# untitled.net
KiCad netlist of a schematic drawn in EAGLE
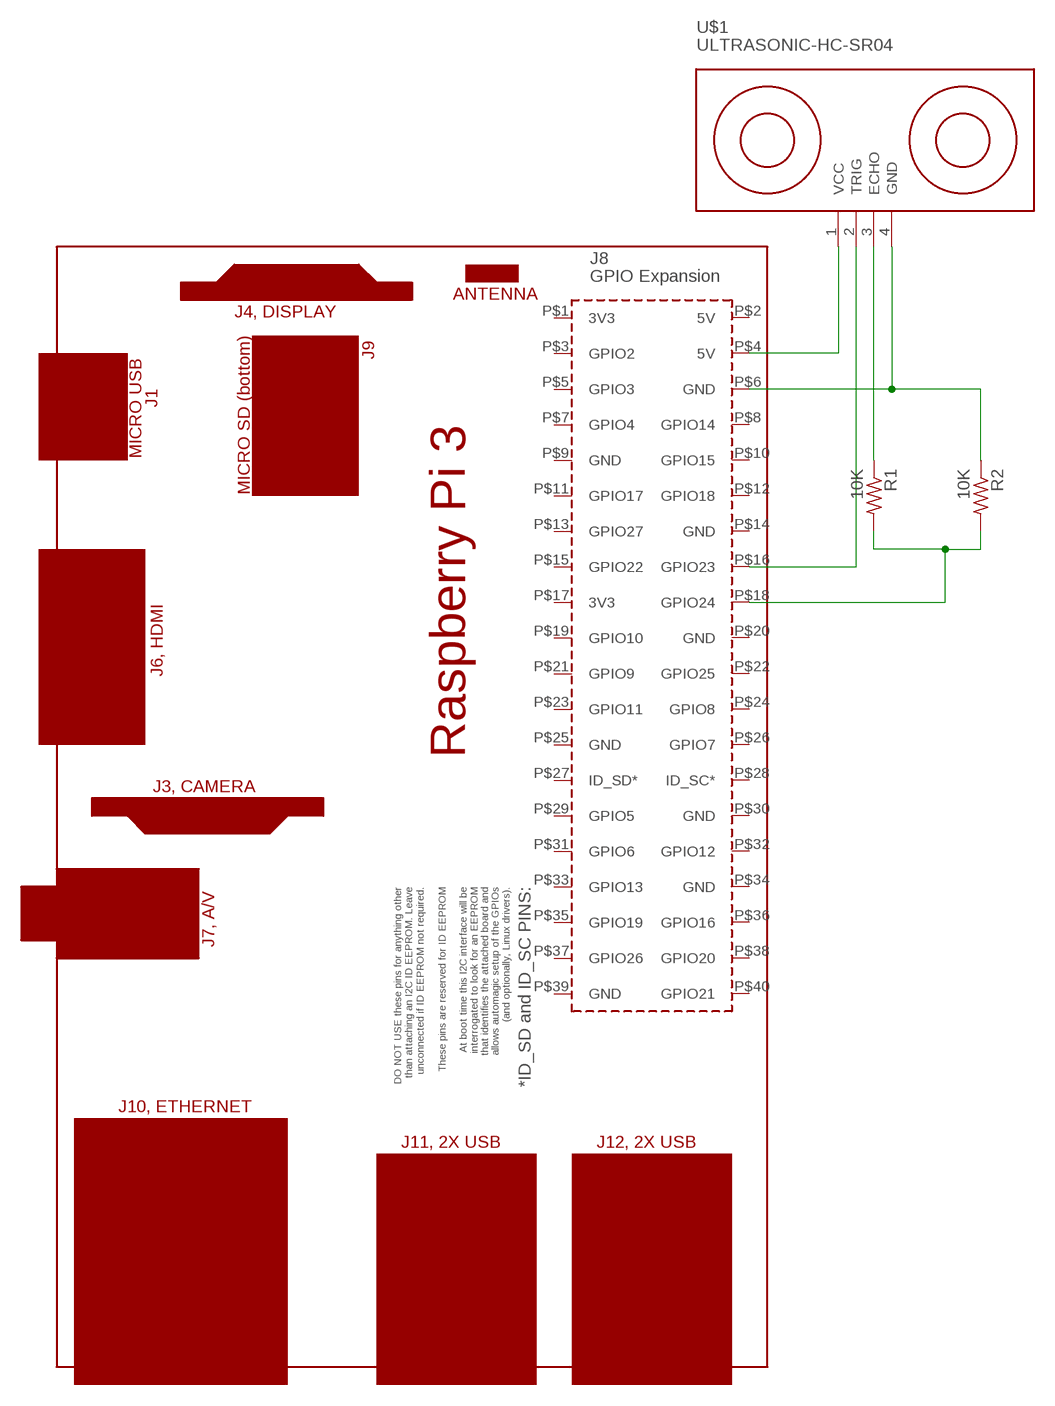
[diagram p0: schematic, sheet 1]

(export (version "E")
  (design (tool "Eeschema 10.0.6"))
  (components
    (comp (ref "PCB1")
      (value "RPI3RPI3")
      (footprint "eagle-import:RPI3")
      (libsource (lib "eagle-import") (part "RPI3RPI3"))
    )
    (comp (ref "R1")
      (value "10K")
      (footprint "eagle-import:0204_5")
      (libsource (lib "eagle-import") (part "R-US_0204/5"))
    )
    (comp (ref "R2")
      (value "10K")
      (footprint "eagle-import:0204_5")
      (libsource (lib "eagle-import") (part "R-US_0204/5"))
    )
    (comp (ref "U$1")
      (value "ULTRASONIC-HC-SR04")
      (footprint "eagle-import:ULTRASONIC-HC-SR04")
      (libsource (lib "eagle-import") (part "ULTRASONIC-HC-SR04"))
    )
  )
  (nets
    (net (code "1") (name "Net-(PCB1-GPIO23)") (class "Default")
      (node (ref "PCB1") (pin "P$16") (pinfunction "GPIO23_P$16") (pintype "bidirectional"))
      (node (ref "U$1") (pin "2") (pinfunction "TRIG_2") (pintype "input"))
    )
    (net (code "2") (name "Net-(PCB1-GPIO24)") (class "Default")
      (node (ref "PCB1") (pin "P$18") (pinfunction "GPIO24_P$18") (pintype "bidirectional"))
      (node (ref "R1") (pin "2") (pinfunction "2_2") (pintype "passive"))
      (node (ref "R2") (pin "2") (pinfunction "2_2") (pintype "passive"))
    )
    (net (code "3") (name "Net-(U$1-ECHO)") (class "Default")
      (node (ref "R1") (pin "1") (pinfunction "1_1") (pintype "passive"))
      (node (ref "U$1") (pin "3") (pinfunction "ECHO_3") (pintype "output"))
    )
    (net (code "4") (name "Net-(U$1-GND)") (class "Default")
      (node (ref "PCB1") (pin "P$6") (pinfunction "GND_P$6") (pintype "bidirectional"))
      (node (ref "R2") (pin "1") (pinfunction "1_1") (pintype "passive"))
      (node (ref "U$1") (pin "4") (pinfunction "GND_4") (pintype "power_in"))
    )
    (net (code "5") (name "Net-(U$1-VCC)") (class "Default")
      (node (ref "PCB1") (pin "P$4") (pinfunction "5V_P$4") (pintype "bidirectional"))
      (node (ref "U$1") (pin "1") (pinfunction "VCC_1") (pintype "power_in"))
    )
    (net (code "6") (name "unconnected-(PCB1-3V3-PadP$1)") (class "Default")
      (node (ref "PCB1") (pin "P$1") (pinfunction "3V3_P$1") (pintype "bidirectional"))
    )
    (net (code "7") (name "unconnected-(PCB1-3V3-PadP$17)") (class "Default")
      (node (ref "PCB1") (pin "P$17") (pinfunction "3V3_P$17") (pintype "bidirectional"))
    )
    (net (code "8") (name "unconnected-(PCB1-5V-PadP$2)") (class "Default")
      (node (ref "PCB1") (pin "P$2") (pinfunction "5V_P$2") (pintype "bidirectional"))
    )
    (net (code "9") (name "unconnected-(PCB1-GND-PadP$9)") (class "Default")
      (node (ref "PCB1") (pin "P$9") (pinfunction "GND_P$9") (pintype "bidirectional"))
    )
    (net (code "10") (name "unconnected-(PCB1-GND-PadP$14)") (class "Default")
      (node (ref "PCB1") (pin "P$14") (pinfunction "GND_P$14") (pintype "bidirectional"))
    )
    (net (code "11") (name "unconnected-(PCB1-GND-PadP$20)") (class "Default")
      (node (ref "PCB1") (pin "P$20") (pinfunction "GND_P$20") (pintype "bidirectional"))
    )
    (net (code "12") (name "unconnected-(PCB1-GND-PadP$25)") (class "Default")
      (node (ref "PCB1") (pin "P$25") (pinfunction "GND_P$25") (pintype "bidirectional"))
    )
    (net (code "13") (name "unconnected-(PCB1-GND-PadP$30)") (class "Default")
      (node (ref "PCB1") (pin "P$30") (pinfunction "GND_P$30") (pintype "bidirectional"))
    )
    (net (code "14") (name "unconnected-(PCB1-GND-PadP$34)") (class "Default")
      (node (ref "PCB1") (pin "P$34") (pinfunction "GND_P$34") (pintype "bidirectional"))
    )
    (net (code "15") (name "unconnected-(PCB1-GND-PadP$39)") (class "Default")
      (node (ref "PCB1") (pin "P$39") (pinfunction "GND_P$39") (pintype "bidirectional"))
    )
    (net (code "16") (name "unconnected-(PCB1-GPIO2-PadP$3)") (class "Default")
      (node (ref "PCB1") (pin "P$3") (pinfunction "GPIO2_P$3") (pintype "bidirectional"))
    )
    (net (code "17") (name "unconnected-(PCB1-GPIO3-PadP$5)") (class "Default")
      (node (ref "PCB1") (pin "P$5") (pinfunction "GPIO3_P$5") (pintype "bidirectional"))
    )
    (net (code "18") (name "unconnected-(PCB1-GPIO4-PadP$7)") (class "Default")
      (node (ref "PCB1") (pin "P$7") (pinfunction "GPIO4_P$7") (pintype "bidirectional"))
    )
    (net (code "19") (name "unconnected-(PCB1-GPIO5-PadP$29)") (class "Default")
      (node (ref "PCB1") (pin "P$29") (pinfunction "GPIO5_P$29") (pintype "bidirectional"))
    )
    (net (code "20") (name "unconnected-(PCB1-GPIO6-PadP$31)") (class "Default")
      (node (ref "PCB1") (pin "P$31") (pinfunction "GPIO6_P$31") (pintype "bidirectional"))
    )
    (net (code "21") (name "unconnected-(PCB1-GPIO7-PadP$26)") (class "Default")
      (node (ref "PCB1") (pin "P$26") (pinfunction "GPIO7_P$26") (pintype "bidirectional"))
    )
    (net (code "22") (name "unconnected-(PCB1-GPIO8-PadP$24)") (class "Default")
      (node (ref "PCB1") (pin "P$24") (pinfunction "GPIO8_P$24") (pintype "bidirectional"))
    )
    (net (code "23") (name "unconnected-(PCB1-GPIO9-PadP$21)") (class "Default")
      (node (ref "PCB1") (pin "P$21") (pinfunction "GPIO9_P$21") (pintype "bidirectional"))
    )
    (net (code "24") (name "unconnected-(PCB1-GPIO10-PadP$19)") (class "Default")
      (node (ref "PCB1") (pin "P$19") (pinfunction "GPIO10_P$19") (pintype "bidirectional"))
    )
    (net (code "25") (name "unconnected-(PCB1-GPIO11-PadP$23)") (class "Default")
      (node (ref "PCB1") (pin "P$23") (pinfunction "GPIO11_P$23") (pintype "bidirectional"))
    )
    (net (code "26") (name "unconnected-(PCB1-GPIO12-PadP$32)") (class "Default")
      (node (ref "PCB1") (pin "P$32") (pinfunction "GPIO12_P$32") (pintype "bidirectional"))
    )
    (net (code "27") (name "unconnected-(PCB1-GPIO13-PadP$33)") (class "Default")
      (node (ref "PCB1") (pin "P$33") (pinfunction "GPIO13_P$33") (pintype "bidirectional"))
    )
    (net (code "28") (name "unconnected-(PCB1-GPIO14-PadP$8)") (class "Default")
      (node (ref "PCB1") (pin "P$8") (pinfunction "GPIO14_P$8") (pintype "bidirectional"))
    )
    (net (code "29") (name "unconnected-(PCB1-GPIO15-PadP$10)") (class "Default")
      (node (ref "PCB1") (pin "P$10") (pinfunction "GPIO15_P$10") (pintype "bidirectional"))
    )
    (net (code "30") (name "unconnected-(PCB1-GPIO16-PadP$36)") (class "Default")
      (node (ref "PCB1") (pin "P$36") (pinfunction "GPIO16_P$36") (pintype "bidirectional"))
    )
    (net (code "31") (name "unconnected-(PCB1-GPIO17-PadP$11)") (class "Default")
      (node (ref "PCB1") (pin "P$11") (pinfunction "GPIO17_P$11") (pintype "bidirectional"))
    )
    (net (code "32") (name "unconnected-(PCB1-GPIO18-PadP$12)") (class "Default")
      (node (ref "PCB1") (pin "P$12") (pinfunction "GPIO18_P$12") (pintype "bidirectional"))
    )
    (net (code "33") (name "unconnected-(PCB1-GPIO19-PadP$35)") (class "Default")
      (node (ref "PCB1") (pin "P$35") (pinfunction "GPIO19_P$35") (pintype "bidirectional"))
    )
    (net (code "34") (name "unconnected-(PCB1-GPIO20-PadP$38)") (class "Default")
      (node (ref "PCB1") (pin "P$38") (pinfunction "GPIO20_P$38") (pintype "bidirectional"))
    )
    (net (code "35") (name "unconnected-(PCB1-GPIO21-PadP$40)") (class "Default")
      (node (ref "PCB1") (pin "P$40") (pinfunction "GPIO21_P$40") (pintype "bidirectional"))
    )
    (net (code "36") (name "unconnected-(PCB1-GPIO22-PadP$15)") (class "Default")
      (node (ref "PCB1") (pin "P$15") (pinfunction "GPIO22_P$15") (pintype "bidirectional"))
    )
    (net (code "37") (name "unconnected-(PCB1-GPIO25-PadP$22)") (class "Default")
      (node (ref "PCB1") (pin "P$22") (pinfunction "GPIO25_P$22") (pintype "bidirectional"))
    )
    (net (code "38") (name "unconnected-(PCB1-GPIO26-PadP$37)") (class "Default")
      (node (ref "PCB1") (pin "P$37") (pinfunction "GPIO26_P$37") (pintype "bidirectional"))
    )
    (net (code "39") (name "unconnected-(PCB1-GPIO27-PadP$13)") (class "Default")
      (node (ref "PCB1") (pin "P$13") (pinfunction "GPIO27_P$13") (pintype "bidirectional"))
    )
    (net (code "40") (name "unconnected-(PCB1-ID_SC*-PadP$28)") (class "Default")
      (node (ref "PCB1") (pin "P$28") (pinfunction "ID_SC*_P$28") (pintype "bidirectional"))
    )
    (net (code "41") (name "unconnected-(PCB1-ID_SD*-PadP$27)") (class "Default")
      (node (ref "PCB1") (pin "P$27") (pinfunction "ID_SD*_P$27") (pintype "bidirectional"))
    )
  )
)
